# EFPR-HPTECH_V1_2.net
KiCad netlist of a schematic drawn in Altium Designer
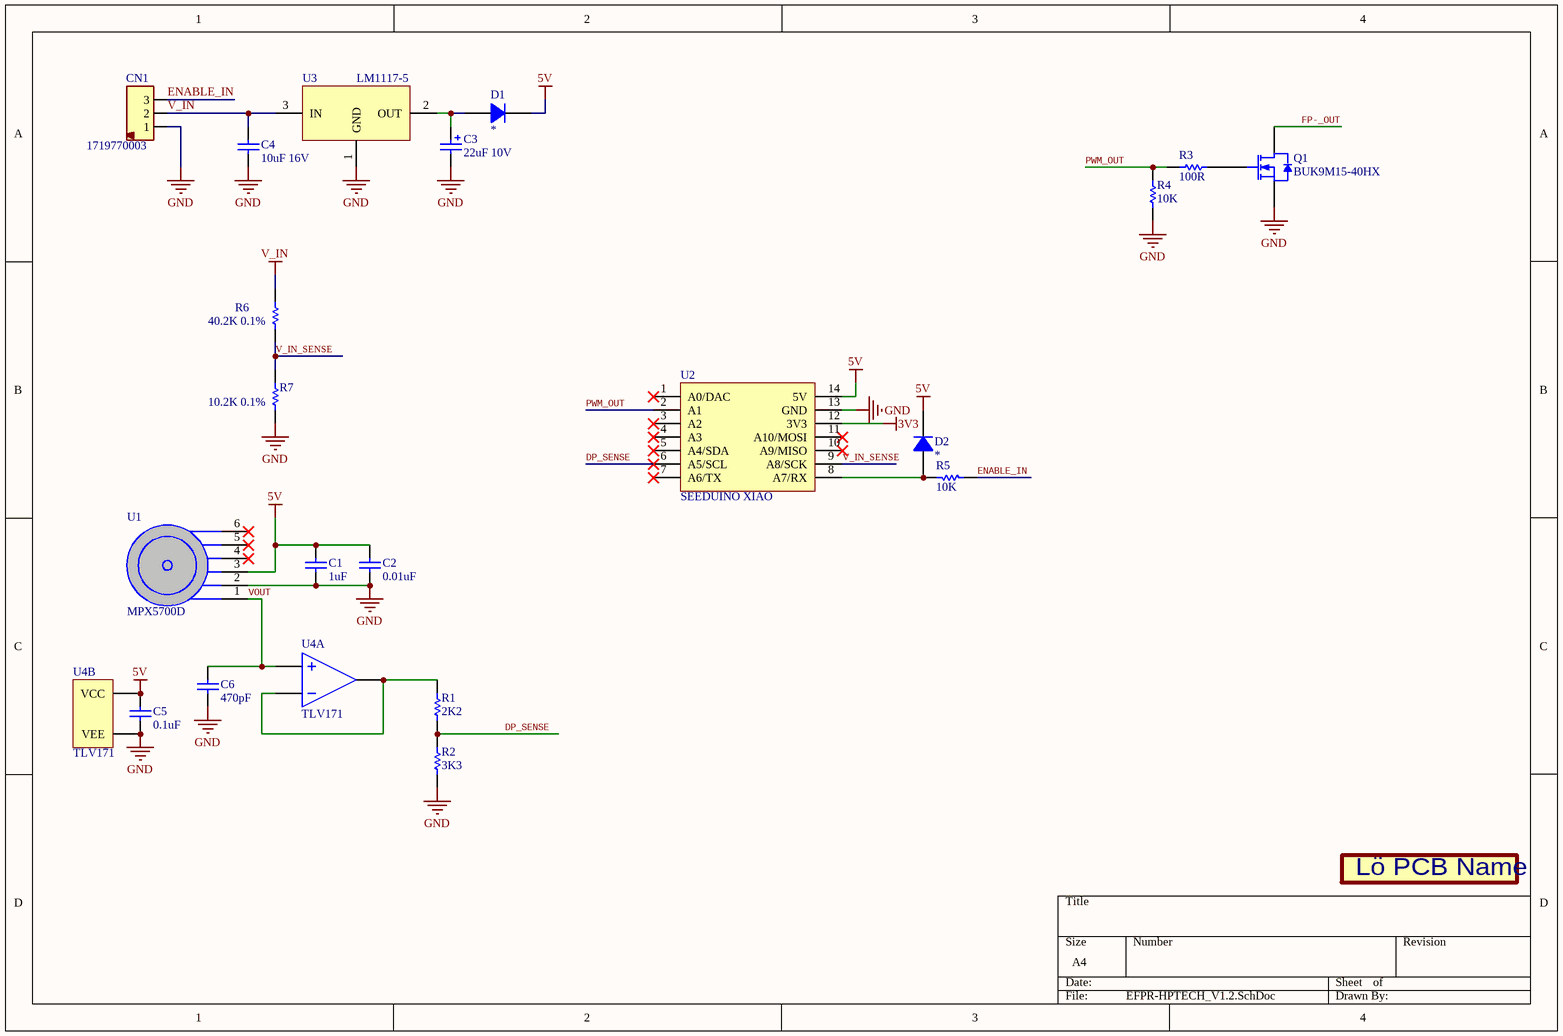
[diagram p0: EFPR-HPTECH_V1.2.SchDoc]

(export (version "E")
  (design (tool "Eeschema 10.0.6"))
  (components
    (comp (ref "C1")
      (value "1uF")
      (footprint "0805S")
      (description "Small Capacitor")
      (libsource (lib "misc") (part "Cap Semi"))
    )
    (comp (ref "C2")
      (value "0.01uF")
      (footprint "0603s")
      (description "Small Capacitor")
      (libsource (lib "misc") (part "Cap Semi"))
    )
    (comp (ref "C3")
      (value "22uF 10V")
      (footprint "C1206")
      (description "Pol. Capacitor")
      (libsource (lib "misc") (part "Cap Pol"))
    )
    (comp (ref "C4")
      (value "10uF 16V")
      (footprint "C0805NP")
      (description "Small Capacitor")
      (libsource (lib "misc") (part "Cap Semi"))
    )
    (comp (ref "C5")
      (value "0.1uF")
      (footprint "0603s")
      (description "Small Capacitor")
      (libsource (lib "misc") (part "Cap Semi"))
    )
    (comp (ref "C6")
      (value "470pF")
      (footprint "0603s")
      (description "Small Capacitor")
      (libsource (lib "misc") (part "Cap Semi"))
    )
    (comp (ref "CN1")
      (value "1719770003")
      (footprint "1719770003")
      (description "CONN HEADER SMD R/A 3POS 2.54MM")
      (fields (field (name "DIGIKEY_PART_NUMBER") "WM22677-ND") (field (name "LIBRARYNAME") "QT_Connectors"))
      (libsource (lib "1719770003") (part "1719770003"))
    )
    (comp (ref "D1")
      (value "*")
      (footprint "SOD323_SC76")
      (description "Standard Diode")
      (libsource (lib "misc") (part "DIODE_STD"))
    )
    (comp (ref "D2")
      (value "*")
      (footprint "SOD323_SC76")
      (description "Standard Diode")
      (libsource (lib "misc") (part "DIODE_STD"))
    )
    (comp (ref "EFPR-HPT v1.2")
      (value "Lo_PCB_Name_15mm")
      (footprint "Logo_Lo_PCB_Name _15mm")
      (description "Lö_PCB_Name_15mm")
      (libsource (lib "ECU v1.1.0") (part "Lö_PCB_Name_15mm"))
    )
    (comp (ref "Q1")
      (value "BUK9M15-40HX")
      (footprint "SOT1210")
      (description "N-Channel MOSFET")
      (libsource (lib "misc") (part "Power N-MOSFET"))
    )
    (comp (ref "R1")
      (value "2K2")
      (footprint "0603s")
      (description "Resistor")
      (libsource (lib "misc") (part "RES_SMD"))
    )
    (comp (ref "R2")
      (value "3K3")
      (footprint "0603s")
      (description "Resistor")
      (libsource (lib "misc") (part "RES_SMD"))
    )
    (comp (ref "R3")
      (value "100R")
      (footprint "0603s")
      (description "Resistor")
      (libsource (lib "misc") (part "RES_SMD"))
    )
    (comp (ref "R4")
      (value "10K")
      (footprint "0603s")
      (description "Resistor")
      (libsource (lib "misc") (part "RES_SMD"))
    )
    (comp (ref "R5")
      (value "10K")
      (footprint "0603s")
      (description "Resistor")
      (libsource (lib "misc") (part "RES_SMD"))
    )
    (comp (ref "R6")
      (value "40.2K 0.1%")
      (footprint "0603s")
      (description "Resistor")
      (libsource (lib "misc") (part "RES_SMD"))
    )
    (comp (ref "R7")
      (value "10.2K 0.1%")
      (footprint "0603s")
      (description "Resistor")
      (libsource (lib "misc") (part "RES_SMD"))
    )
    (comp (ref "U1") (value "MPX5700D") (footprint "MPX5700D") (libsource (lib "misc") (part "MPX5700D")))
    (comp (ref "U2")
      (value "SEEDUINO XIAO")
      (footprint "SEEDUINO_XIAO")
      (libsource (lib "quaternium") (part "SEEDUIONA_XIAO"))
    )
    (comp (ref "U3")
      (value "LM1117-5")
      (footprint "SOT223_REG")
      (description "Voltage Regulator (LDO); Output in Tab")
      (libsource (lib "power") (part "LDO_TAB"))
    )
    (comp (ref "U4")
      (value "TLV171")
      (footprint "SOT23-5")
      (description "Single Operational Amplifier")
      (libsource (lib "misc") (part "OP_AMP1"))
    )
  )
  (nets
    (net (code "1") (name "/DP_SENSE") (class "Default")
      (node (ref "R1") (pin "2") (pinfunction "2_2") (pintype "passive"))
      (node (ref "R2") (pin "1") (pinfunction "1_1") (pintype "passive"))
      (node (ref "U2") (pin "6") (pinfunction "A5/SCL_6") (pintype "passive"))
    )
    (net (code "2") (name "/ENABLE_IN") (class "Default")
      (node (ref "CN1") (pin "3") (pinfunction "3_3") (pintype "passive"))
      (node (ref "R5") (pin "2") (pinfunction "2_2") (pintype "passive"))
    )
    (net (code "3") (name "/FP-_OUT") (class "Default")
      (node (ref "Q1") (pin "2") (pinfunction "D_2") (pintype "passive"))
    )
    (net (code "4") (name "/PWM_OUT") (class "Default")
      (node (ref "R3") (pin "1") (pinfunction "1_1") (pintype "passive"))
      (node (ref "R4") (pin "2") (pinfunction "2_2") (pintype "passive"))
      (node (ref "U2") (pin "2") (pinfunction "A1_2") (pintype "passive"))
    )
    (net (code "5") (name "/VOUT") (class "Default")
      (node (ref "C6") (pin "2") (pinfunction "2_2") (pintype "passive"))
      (node (ref "U1") (pin "1") (pinfunction "1_1") (pintype "passive"))
      (node (ref "U4") (pin "IP") (pinfunction "+IN1_IP") (pintype "passive"))
    )
    (net (code "6") (name "/V_IN_SENSE") (class "Default")
      (node (ref "R6") (pin "2") (pinfunction "2_2") (pintype "passive"))
      (node (ref "R7") (pin "2") (pinfunction "2_2") (pintype "passive"))
      (node (ref "U2") (pin "9") (pinfunction "A8/SCK_9") (pintype "passive"))
    )
    (net (code "7") (name "3V3") (class "Default")
      (node (ref "U2") (pin "12") (pinfunction "3V3_12") (pintype "passive"))
    )
    (net (code "8") (name "5V") (class "Default")
      (node (ref "C1") (pin "2") (pinfunction "2_2") (pintype "passive"))
      (node (ref "C2") (pin "2") (pinfunction "2_2") (pintype "passive"))
      (node (ref "C5") (pin "2") (pinfunction "2_2") (pintype "passive"))
      (node (ref "D1") (pin "K") (pinfunction "K_K") (pintype "passive"))
      (node (ref "D2") (pin "K") (pinfunction "K_K") (pintype "passive"))
      (node (ref "U1") (pin "3") (pinfunction "3_3") (pintype "passive"))
      (node (ref "U2") (pin "14") (pinfunction "5V_14") (pintype "passive"))
      (node (ref "U4") (pin "VCC") (pinfunction "VCC_VCC") (pintype "power_in"))
    )
    (net (code "9") (name "GND") (class "Default")
      (node (ref "C1") (pin "1") (pinfunction "1_1") (pintype "passive"))
      (node (ref "C2") (pin "1") (pinfunction "1_1") (pintype "passive"))
      (node (ref "C3") (pin "2") (pinfunction "2_2") (pintype "passive"))
      (node (ref "C4") (pin "1") (pinfunction "1_1") (pintype "passive"))
      (node (ref "C5") (pin "1") (pinfunction "1_1") (pintype "passive"))
      (node (ref "C6") (pin "1") (pinfunction "1_1") (pintype "passive"))
      (node (ref "CN1") (pin "1") (pinfunction "1_1") (pintype "passive"))
      (node (ref "Q1") (pin "3") (pinfunction "S_3") (pintype "passive"))
      (node (ref "R2") (pin "2") (pinfunction "2_2") (pintype "passive"))
      (node (ref "R4") (pin "1") (pinfunction "1_1") (pintype "passive"))
      (node (ref "R7") (pin "1") (pinfunction "1_1") (pintype "passive"))
      (node (ref "U1") (pin "2") (pinfunction "2_2") (pintype "passive"))
      (node (ref "U2") (pin "13") (pinfunction "GND_13") (pintype "passive"))
      (node (ref "U3") (pin "1") (pinfunction "GND_1") (pintype "power_in"))
      (node (ref "U4") (pin "VEE") (pinfunction "VEE_VEE") (pintype "power_in"))
    )
    (net (code "10") (name "Net-(Q1-G)") (class "Default")
      (node (ref "Q1") (pin "1") (pinfunction "G_1") (pintype "passive"))
      (node (ref "R3") (pin "2") (pinfunction "2_2") (pintype "passive"))
    )
    (net (code "11") (name "Net-(U2-A7{slash}RX)") (class "Default")
      (node (ref "D2") (pin "A") (pinfunction "A_A") (pintype "passive"))
      (node (ref "R5") (pin "1") (pinfunction "1_1") (pintype "passive"))
      (node (ref "U2") (pin "8") (pinfunction "A7/RX_8") (pintype "passive"))
    )
    (net (code "12") (name "Net-(U3-OUT)") (class "Default")
      (node (ref "C3") (pin "1") (pinfunction "1_1") (pintype "passive"))
      (node (ref "D1") (pin "A") (pinfunction "A_A") (pintype "passive"))
      (node (ref "U3") (pin "2") (pinfunction "OUT_2") (pintype "power_in"))
    )
    (net (code "13") (name "Net-(U4A--IN1)") (class "Default")
      (node (ref "R1") (pin "1") (pinfunction "1_1") (pintype "passive"))
      (node (ref "U4") (pin "IM") (pinfunction "-IN1_IM") (pintype "passive"))
      (node (ref "U4") (pin "O") (pinfunction "OUT1_O") (pintype "open_collector"))
    )
    (net (code "14") (name "V_IN") (class "Default")
      (node (ref "C4") (pin "2") (pinfunction "2_2") (pintype "passive"))
      (node (ref "CN1") (pin "2") (pinfunction "2_2") (pintype "passive"))
      (node (ref "R6") (pin "1") (pinfunction "1_1") (pintype "passive"))
      (node (ref "U3") (pin "3") (pinfunction "IN_3") (pintype "power_in"))
    )
    (net (code "15") (name "unconnected-(U1-Pad4)") (class "Default")
      (node (ref "U1") (pin "4") (pinfunction "4_4") (pintype "passive+no_connect"))
    )
    (net (code "16") (name "unconnected-(U1-Pad5)") (class "Default")
      (node (ref "U1") (pin "5") (pinfunction "5_5") (pintype "passive+no_connect"))
    )
    (net (code "17") (name "unconnected-(U1-Pad6)") (class "Default")
      (node (ref "U1") (pin "6") (pinfunction "6_6") (pintype "passive+no_connect"))
    )
    (net (code "18") (name "unconnected-(U2-A0{slash}DAC-Pad1)") (class "Default")
      (node (ref "U2") (pin "1") (pinfunction "A0/DAC_1") (pintype "passive+no_connect"))
    )
    (net (code "19") (name "unconnected-(U2-A2-Pad3)") (class "Default")
      (node (ref "U2") (pin "3") (pinfunction "A2_3") (pintype "passive+no_connect"))
    )
    (net (code "20") (name "unconnected-(U2-A3-Pad4)") (class "Default")
      (node (ref "U2") (pin "4") (pinfunction "A3_4") (pintype "passive+no_connect"))
    )
    (net (code "21") (name "unconnected-(U2-A4{slash}SDA-Pad5)") (class "Default")
      (node (ref "U2") (pin "5") (pinfunction "A4/SDA_5") (pintype "passive+no_connect"))
    )
    (net (code "22") (name "unconnected-(U2-A6{slash}TX-Pad7)") (class "Default")
      (node (ref "U2") (pin "7") (pinfunction "A6/TX_7") (pintype "passive+no_connect"))
    )
    (net (code "23") (name "unconnected-(U2-A9{slash}MISO-Pad10)") (class "Default")
      (node (ref "U2") (pin "10") (pinfunction "A9/MISO_10") (pintype "passive+no_connect"))
    )
    (net (code "24") (name "unconnected-(U2-A10{slash}MOSI-Pad11)") (class "Default")
      (node (ref "U2") (pin "11") (pinfunction "A10/MOSI_11") (pintype "passive+no_connect"))
    )
  )
)
